# R205X.net
KiCad netlist of a schematic drawn in EAGLE
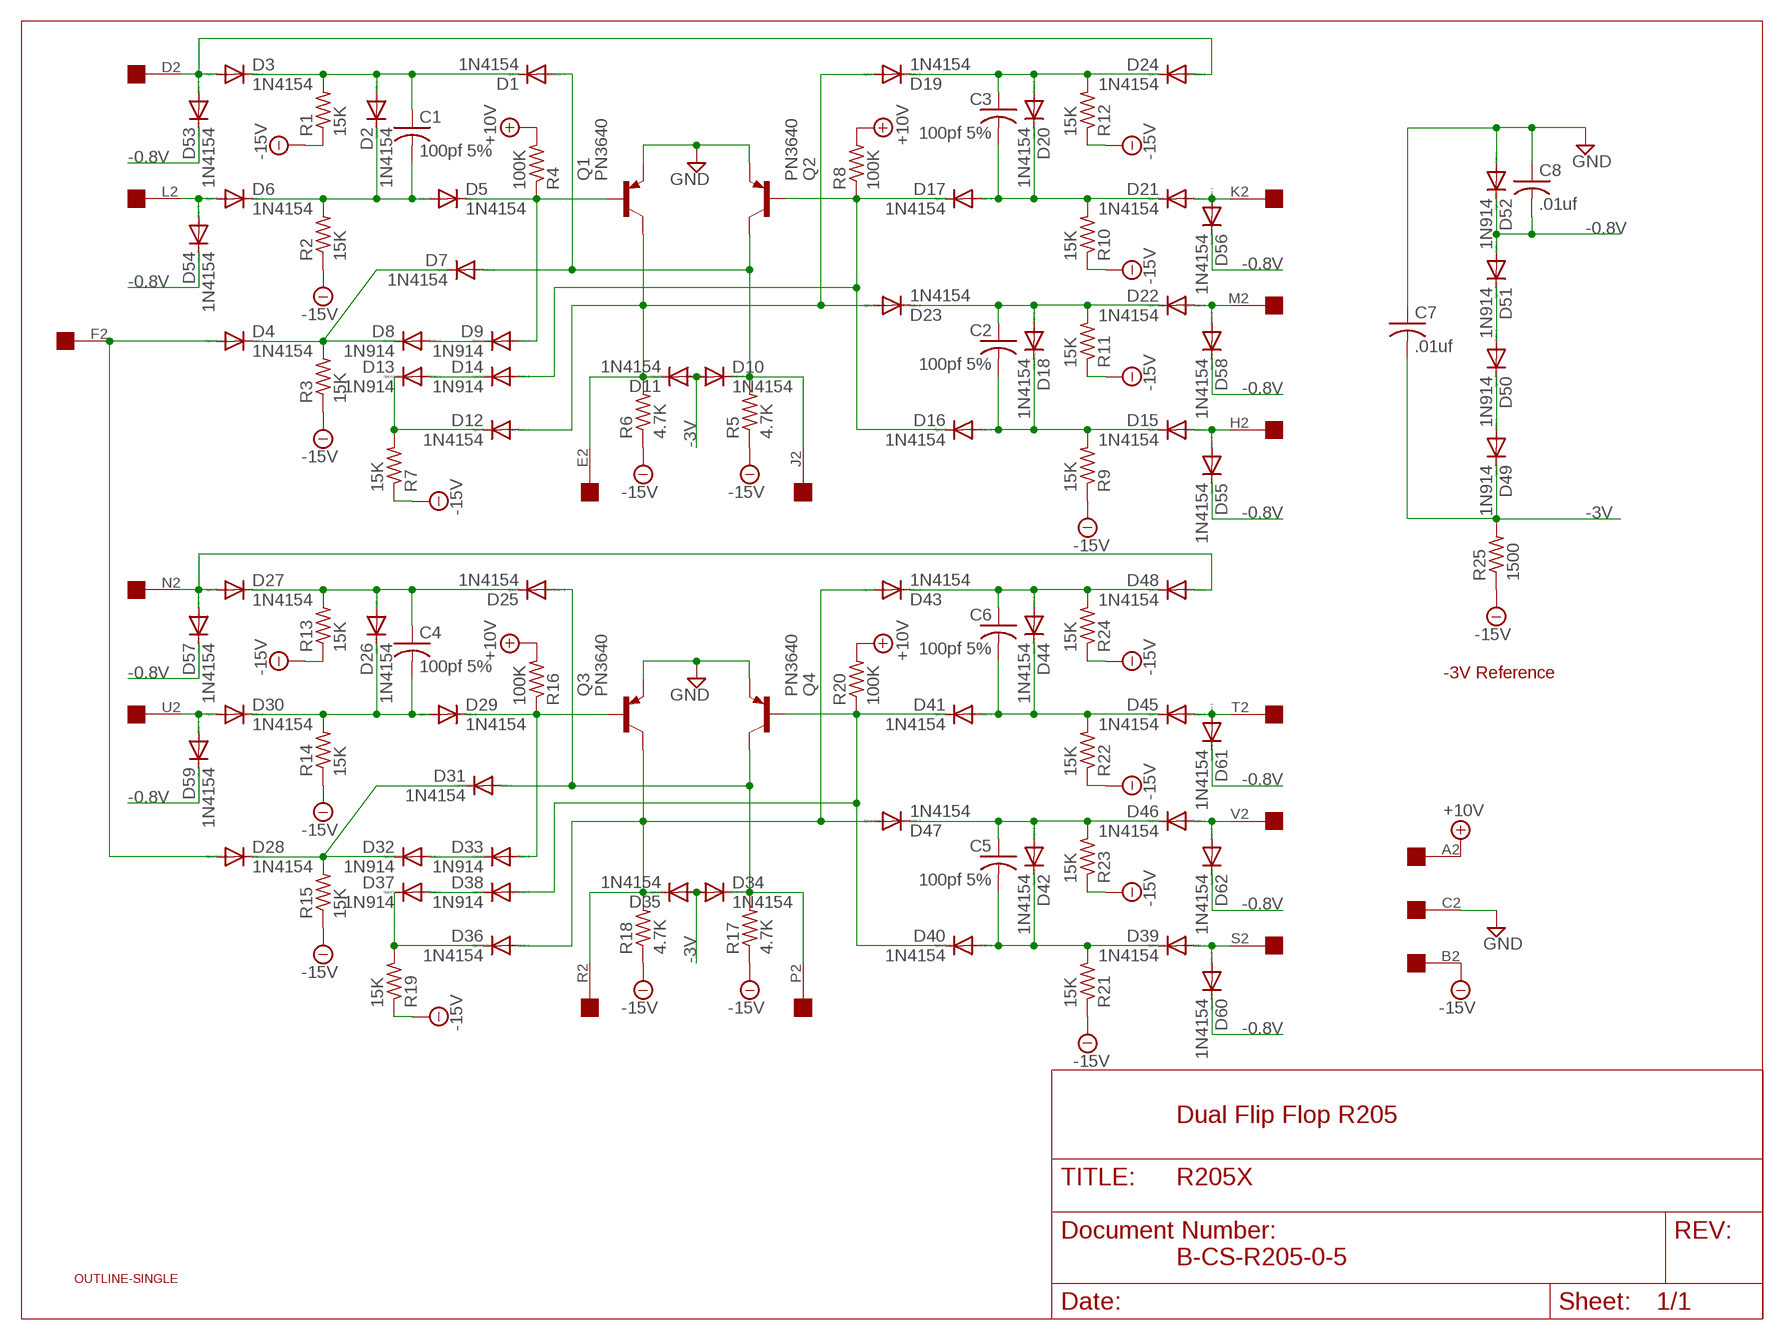
[diagram p0: schematic, sheet 1]

(export (version "E")
  (design (tool "Eeschema 10.0.6"))
  (components
    (comp (ref "C1")
      (value "100pf 5%")
      (footprint "eagle-import:C050-025X075")
      (libsource (lib "eagle-import") (part "C-US050-025X075"))
    )
    (comp (ref "C2")
      (value "100pf 5%")
      (footprint "eagle-import:C050-025X075")
      (libsource (lib "eagle-import") (part "C-US050-025X075"))
    )
    (comp (ref "C3")
      (value "100pf 5%")
      (footprint "eagle-import:C050-025X075")
      (libsource (lib "eagle-import") (part "C-US050-025X075"))
    )
    (comp (ref "C4")
      (value "100pf 5%")
      (footprint "eagle-import:C050-025X075")
      (libsource (lib "eagle-import") (part "C-US050-025X075"))
    )
    (comp (ref "C5")
      (value "100pf 5%")
      (footprint "eagle-import:C050-025X075")
      (libsource (lib "eagle-import") (part "C-US050-025X075"))
    )
    (comp (ref "C6")
      (value "100pf 5%")
      (footprint "eagle-import:C050-025X075")
      (libsource (lib "eagle-import") (part "C-US050-025X075"))
    )
    (comp (ref "C7")
      (value ".01uf")
      (footprint "eagle-import:C050-025X075")
      (libsource (lib "eagle-import") (part "C-US050-025X075"))
    )
    (comp (ref "C8")
      (value ".01uf")
      (footprint "eagle-import:C050-025X075")
      (libsource (lib "eagle-import") (part "C-US050-025X075"))
    )
    (comp (ref "D1")
      (value "1N4154")
      (footprint "eagle-import:DO35-10")
      (libsource (lib "eagle-import") (part "1N4148DO35-10"))
    )
    (comp (ref "D2")
      (value "1N4154")
      (footprint "eagle-import:DO35-10")
      (libsource (lib "eagle-import") (part "1N4148DO35-10"))
    )
    (comp (ref "D3")
      (value "1N4154")
      (footprint "eagle-import:DO35-10")
      (libsource (lib "eagle-import") (part "1N4148DO35-10"))
    )
    (comp (ref "D4")
      (value "1N4154")
      (footprint "eagle-import:DO35-10")
      (libsource (lib "eagle-import") (part "1N4148DO35-10"))
    )
    (comp (ref "D5")
      (value "1N4154")
      (footprint "eagle-import:DO35-10")
      (libsource (lib "eagle-import") (part "1N4148DO35-10"))
    )
    (comp (ref "D6")
      (value "1N4154")
      (footprint "eagle-import:DO35-10")
      (libsource (lib "eagle-import") (part "1N4148DO35-10"))
    )
    (comp (ref "D7")
      (value "1N4154")
      (footprint "eagle-import:DO35-10")
      (libsource (lib "eagle-import") (part "1N4148DO35-10"))
    )
    (comp (ref "D8")
      (value "1N914")
      (footprint "eagle-import:DO35-10")
      (libsource (lib "eagle-import") (part "1N4148DO35-10"))
    )
    (comp (ref "D9")
      (value "1N914")
      (footprint "eagle-import:DO35-10")
      (libsource (lib "eagle-import") (part "1N4148DO35-10"))
    )
    (comp (ref "D10")
      (value "1N4154")
      (footprint "eagle-import:DO35-10")
      (libsource (lib "eagle-import") (part "1N4148DO35-10"))
    )
    (comp (ref "D11")
      (value "1N4154")
      (footprint "eagle-import:DO35-10")
      (libsource (lib "eagle-import") (part "1N4148DO35-10"))
    )
    (comp (ref "D12")
      (value "1N4154")
      (footprint "eagle-import:DO35-10")
      (libsource (lib "eagle-import") (part "1N4148DO35-10"))
    )
    (comp (ref "D13")
      (value "1N914")
      (footprint "eagle-import:DO35-10")
      (libsource (lib "eagle-import") (part "1N4148DO35-10"))
    )
    (comp (ref "D14")
      (value "1N914")
      (footprint "eagle-import:DO35-10")
      (libsource (lib "eagle-import") (part "1N4148DO35-10"))
    )
    (comp (ref "D15")
      (value "1N4154")
      (footprint "eagle-import:DO35-10")
      (libsource (lib "eagle-import") (part "1N4148DO35-10"))
    )
    (comp (ref "D16")
      (value "1N4154")
      (footprint "eagle-import:DO35-10")
      (libsource (lib "eagle-import") (part "1N4148DO35-10"))
    )
    (comp (ref "D17")
      (value "1N4154")
      (footprint "eagle-import:DO35-10")
      (libsource (lib "eagle-import") (part "1N4148DO35-10"))
    )
    (comp (ref "D18")
      (value "1N4154")
      (footprint "eagle-import:DO35-10")
      (libsource (lib "eagle-import") (part "1N4148DO35-10"))
    )
    (comp (ref "D19")
      (value "1N4154")
      (footprint "eagle-import:DO35-10")
      (libsource (lib "eagle-import") (part "1N4148DO35-10"))
    )
    (comp (ref "D20")
      (value "1N4154")
      (footprint "eagle-import:DO35-10")
      (libsource (lib "eagle-import") (part "1N4148DO35-10"))
    )
    (comp (ref "D21")
      (value "1N4154")
      (footprint "eagle-import:DO35-10")
      (libsource (lib "eagle-import") (part "1N4148DO35-10"))
    )
    (comp (ref "D22")
      (value "1N4154")
      (footprint "eagle-import:DO35-10")
      (libsource (lib "eagle-import") (part "1N4148DO35-10"))
    )
    (comp (ref "D23")
      (value "1N4154")
      (footprint "eagle-import:DO35-10")
      (libsource (lib "eagle-import") (part "1N4148DO35-10"))
    )
    (comp (ref "D24")
      (value "1N4154")
      (footprint "eagle-import:DO35-10")
      (libsource (lib "eagle-import") (part "1N4148DO35-10"))
    )
    (comp (ref "D25")
      (value "1N4154")
      (footprint "eagle-import:DO35-10")
      (libsource (lib "eagle-import") (part "1N4148DO35-10"))
    )
    (comp (ref "D26")
      (value "1N4154")
      (footprint "eagle-import:DO35-10")
      (libsource (lib "eagle-import") (part "1N4148DO35-10"))
    )
    (comp (ref "D27")
      (value "1N4154")
      (footprint "eagle-import:DO35-10")
      (libsource (lib "eagle-import") (part "1N4148DO35-10"))
    )
    (comp (ref "D28")
      (value "1N4154")
      (footprint "eagle-import:DO35-10")
      (libsource (lib "eagle-import") (part "1N4148DO35-10"))
    )
    (comp (ref "D29")
      (value "1N4154")
      (footprint "eagle-import:DO35-10")
      (libsource (lib "eagle-import") (part "1N4148DO35-10"))
    )
    (comp (ref "D30")
      (value "1N4154")
      (footprint "eagle-import:DO35-10")
      (libsource (lib "eagle-import") (part "1N4148DO35-10"))
    )
    (comp (ref "D31")
      (value "1N4154")
      (footprint "eagle-import:DO35-10")
      (libsource (lib "eagle-import") (part "1N4148DO35-10"))
    )
    (comp (ref "D32")
      (value "1N914")
      (footprint "eagle-import:DO35-10")
      (libsource (lib "eagle-import") (part "1N4148DO35-10"))
    )
    (comp (ref "D33")
      (value "1N914")
      (footprint "eagle-import:DO35-10")
      (libsource (lib "eagle-import") (part "1N4148DO35-10"))
    )
    (comp (ref "D34")
      (value "1N4154")
      (footprint "eagle-import:DO35-10")
      (libsource (lib "eagle-import") (part "1N4148DO35-10"))
    )
    (comp (ref "D35")
      (value "1N4154")
      (footprint "eagle-import:DO35-10")
      (libsource (lib "eagle-import") (part "1N4148DO35-10"))
    )
    (comp (ref "D36")
      (value "1N4154")
      (footprint "eagle-import:DO35-10")
      (libsource (lib "eagle-import") (part "1N4148DO35-10"))
    )
    (comp (ref "D37")
      (value "1N914")
      (footprint "eagle-import:DO35-10")
      (libsource (lib "eagle-import") (part "1N4148DO35-10"))
    )
    (comp (ref "D38")
      (value "1N914")
      (footprint "eagle-import:DO35-10")
      (libsource (lib "eagle-import") (part "1N4148DO35-10"))
    )
    (comp (ref "D39")
      (value "1N4154")
      (footprint "eagle-import:DO35-10")
      (libsource (lib "eagle-import") (part "1N4148DO35-10"))
    )
    (comp (ref "D40")
      (value "1N4154")
      (footprint "eagle-import:DO35-10")
      (libsource (lib "eagle-import") (part "1N4148DO35-10"))
    )
    (comp (ref "D41")
      (value "1N4154")
      (footprint "eagle-import:DO35-10")
      (libsource (lib "eagle-import") (part "1N4148DO35-10"))
    )
    (comp (ref "D42")
      (value "1N4154")
      (footprint "eagle-import:DO35-10")
      (libsource (lib "eagle-import") (part "1N4148DO35-10"))
    )
    (comp (ref "D43")
      (value "1N4154")
      (footprint "eagle-import:DO35-10")
      (libsource (lib "eagle-import") (part "1N4148DO35-10"))
    )
    (comp (ref "D44")
      (value "1N4154")
      (footprint "eagle-import:DO35-10")
      (libsource (lib "eagle-import") (part "1N4148DO35-10"))
    )
    (comp (ref "D45")
      (value "1N4154")
      (footprint "eagle-import:DO35-10")
      (libsource (lib "eagle-import") (part "1N4148DO35-10"))
    )
    (comp (ref "D46")
      (value "1N4154")
      (footprint "eagle-import:DO35-10")
      (libsource (lib "eagle-import") (part "1N4148DO35-10"))
    )
    (comp (ref "D47")
      (value "1N4154")
      (footprint "eagle-import:DO35-10")
      (libsource (lib "eagle-import") (part "1N4148DO35-10"))
    )
    (comp (ref "D48")
      (value "1N4154")
      (footprint "eagle-import:DO35-10")
      (libsource (lib "eagle-import") (part "1N4148DO35-10"))
    )
    (comp (ref "D49")
      (value "1N914")
      (footprint "eagle-import:DO35-10")
      (libsource (lib "eagle-import") (part "1N4148DO35-10"))
    )
    (comp (ref "D50")
      (value "1N914")
      (footprint "eagle-import:DO35-10")
      (libsource (lib "eagle-import") (part "1N4148DO35-10"))
    )
    (comp (ref "D51")
      (value "1N914")
      (footprint "eagle-import:DO35-10")
      (libsource (lib "eagle-import") (part "1N4148DO35-10"))
    )
    (comp (ref "D52")
      (value "1N914")
      (footprint "eagle-import:DO35-10")
      (libsource (lib "eagle-import") (part "1N4148DO35-10"))
    )
    (comp (ref "D53")
      (value "1N4154")
      (footprint "eagle-import:DO35-10")
      (libsource (lib "eagle-import") (part "1N4148DO35-10"))
    )
    (comp (ref "D54")
      (value "1N4154")
      (footprint "eagle-import:DO35-10")
      (libsource (lib "eagle-import") (part "1N4148DO35-10"))
    )
    (comp (ref "D55")
      (value "1N4154")
      (footprint "eagle-import:DO35-10")
      (libsource (lib "eagle-import") (part "1N4148DO35-10"))
    )
    (comp (ref "D56")
      (value "1N4154")
      (footprint "eagle-import:DO35-10")
      (libsource (lib "eagle-import") (part "1N4148DO35-10"))
    )
    (comp (ref "D57")
      (value "1N4154")
      (footprint "eagle-import:DO35-10")
      (libsource (lib "eagle-import") (part "1N4148DO35-10"))
    )
    (comp (ref "D58")
      (value "1N4154")
      (footprint "eagle-import:DO35-10")
      (libsource (lib "eagle-import") (part "1N4148DO35-10"))
    )
    (comp (ref "D59")
      (value "1N4154")
      (footprint "eagle-import:DO35-10")
      (libsource (lib "eagle-import") (part "1N4148DO35-10"))
    )
    (comp (ref "D60")
      (value "1N4154")
      (footprint "eagle-import:DO35-10")
      (libsource (lib "eagle-import") (part "1N4148DO35-10"))
    )
    (comp (ref "D61")
      (value "1N4154")
      (footprint "eagle-import:DO35-10")
      (libsource (lib "eagle-import") (part "1N4148DO35-10"))
    )
    (comp (ref "D62")
      (value "1N4154")
      (footprint "eagle-import:DO35-10")
      (libsource (lib "eagle-import") (part "1N4148DO35-10"))
    )
    (comp (ref "Q1")
      (value "PN3640")
      (footprint "eagle-import:TO39")
      (libsource (lib "eagle-import") (part "2N3637"))
    )
    (comp (ref "Q2")
      (value "PN3640")
      (footprint "eagle-import:TO39")
      (libsource (lib "eagle-import") (part "2N3637"))
    )
    (comp (ref "Q3")
      (value "PN3640")
      (footprint "eagle-import:TO39")
      (libsource (lib "eagle-import") (part "2N3637"))
    )
    (comp (ref "Q4")
      (value "PN3640")
      (footprint "eagle-import:TO39")
      (libsource (lib "eagle-import") (part "2N3637"))
    )
    (comp (ref "R1")
      (value "15K")
      (footprint "eagle-import:0207_10")
      (libsource (lib "eagle-import") (part "R-US_0207/10"))
    )
    (comp (ref "R2")
      (value "15K")
      (footprint "eagle-import:0207_10")
      (libsource (lib "eagle-import") (part "R-US_0207/10"))
    )
    (comp (ref "R3")
      (value "15K")
      (footprint "eagle-import:0207_10")
      (libsource (lib "eagle-import") (part "R-US_0207/10"))
    )
    (comp (ref "R4")
      (value "100K")
      (footprint "eagle-import:0207_10")
      (libsource (lib "eagle-import") (part "R-US_0207/10"))
    )
    (comp (ref "R5")
      (value "4.7K")
      (footprint "eagle-import:0207_10")
      (libsource (lib "eagle-import") (part "R-US_0207/10"))
    )
    (comp (ref "R6")
      (value "4.7K")
      (footprint "eagle-import:0207_10")
      (libsource (lib "eagle-import") (part "R-US_0207/10"))
    )
    (comp (ref "R7")
      (value "15K")
      (footprint "eagle-import:0207_10")
      (libsource (lib "eagle-import") (part "R-US_0207/10"))
    )
    (comp (ref "R8")
      (value "100K")
      (footprint "eagle-import:0207_10")
      (libsource (lib "eagle-import") (part "R-US_0207/10"))
    )
    (comp (ref "R9")
      (value "15K")
      (footprint "eagle-import:0207_10")
      (libsource (lib "eagle-import") (part "R-US_0207/10"))
    )
    (comp (ref "R10")
      (value "15K")
      (footprint "eagle-import:0207_10")
      (libsource (lib "eagle-import") (part "R-US_0207/10"))
    )
    (comp (ref "R11")
      (value "15K")
      (footprint "eagle-import:0207_10")
      (libsource (lib "eagle-import") (part "R-US_0207/10"))
    )
    (comp (ref "R12")
      (value "15K")
      (footprint "eagle-import:0207_10")
      (libsource (lib "eagle-import") (part "R-US_0207/10"))
    )
    (comp (ref "R13")
      (value "15K")
      (footprint "eagle-import:0207_10")
      (libsource (lib "eagle-import") (part "R-US_0207/10"))
    )
    (comp (ref "R14")
      (value "15K")
      (footprint "eagle-import:0207_10")
      (libsource (lib "eagle-import") (part "R-US_0207/10"))
    )
    (comp (ref "R15")
      (value "15K")
      (footprint "eagle-import:0207_10")
      (libsource (lib "eagle-import") (part "R-US_0207/10"))
    )
    (comp (ref "R16")
      (value "100K")
      (footprint "eagle-import:0207_10")
      (libsource (lib "eagle-import") (part "R-US_0207/10"))
    )
    (comp (ref "R17")
      (value "4.7K")
      (footprint "eagle-import:0207_10")
      (libsource (lib "eagle-import") (part "R-US_0207/10"))
    )
    (comp (ref "R18")
      (value "4.7K")
      (footprint "eagle-import:0207_10")
      (libsource (lib "eagle-import") (part "R-US_0207/10"))
    )
    (comp (ref "R19")
      (value "15K")
      (footprint "eagle-import:0207_10")
      (libsource (lib "eagle-import") (part "R-US_0207/10"))
    )
    (comp (ref "R20")
      (value "100K")
      (footprint "eagle-import:0207_10")
      (libsource (lib "eagle-import") (part "R-US_0207/10"))
    )
    (comp (ref "R21")
      (value "15K")
      (footprint "eagle-import:0207_10")
      (libsource (lib "eagle-import") (part "R-US_0207/10"))
    )
    (comp (ref "R22")
      (value "15K")
      (footprint "eagle-import:0207_10")
      (libsource (lib "eagle-import") (part "R-US_0207/10"))
    )
    (comp (ref "R23")
      (value "15K")
      (footprint "eagle-import:0207_10")
      (libsource (lib "eagle-import") (part "R-US_0207/10"))
    )
    (comp (ref "R24")
      (value "15K")
      (footprint "eagle-import:0207_10")
      (libsource (lib "eagle-import") (part "R-US_0207/10"))
    )
    (comp (ref "R25")
      (value "1500")
      (footprint "eagle-import:0207_10")
      (libsource (lib "eagle-import") (part "R-US_0207/10"))
    )
    (comp (ref "U$1")
      (value "OUTLINE-SINGLE")
      (footprint "eagle-import:SINGLE")
      (libsource (lib "eagle-import") (part "OUTLINE-SINGLE"))
    )
    (comp (ref "U$2")
      (value "EDGE-1")
      (footprint "eagle-import:EDGE-CON1")
      (libsource (lib "eagle-import") (part "EDGE-1"))
    )
  )
  (nets
    (net (code "1") (name "+10V") (class "Default")
      (node (ref "R16") (pin "2") (pinfunction "2_2") (pintype "passive"))
      (node (ref "R20") (pin "2") (pinfunction "2_2") (pintype "passive"))
      (node (ref "R4") (pin "2") (pinfunction "2_2") (pintype "passive"))
      (node (ref "R8") (pin "2") (pinfunction "2_2") (pintype "passive"))
      (node (ref "U$2") (pin "A2") (pinfunction "1_A2") (pintype "bidirectional"))
    )
    (net (code "2") (name "-15V") (class "Default")
      (node (ref "R1") (pin "1") (pinfunction "1_1") (pintype "passive"))
      (node (ref "R10") (pin "1") (pinfunction "1_1") (pintype "passive"))
      (node (ref "R11") (pin "1") (pinfunction "1_1") (pintype "passive"))
      (node (ref "R12") (pin "1") (pinfunction "1_1") (pintype "passive"))
      (node (ref "R13") (pin "1") (pinfunction "1_1") (pintype "passive"))
      (node (ref "R14") (pin "1") (pinfunction "1_1") (pintype "passive"))
      (node (ref "R15") (pin "1") (pinfunction "1_1") (pintype "passive"))
      (node (ref "R17") (pin "1") (pinfunction "1_1") (pintype "passive"))
      (node (ref "R18") (pin "1") (pinfunction "1_1") (pintype "passive"))
      (node (ref "R19") (pin "1") (pinfunction "1_1") (pintype "passive"))
      (node (ref "R2") (pin "1") (pinfunction "1_1") (pintype "passive"))
      (node (ref "R21") (pin "1") (pinfunction "1_1") (pintype "passive"))
      (node (ref "R22") (pin "1") (pinfunction "1_1") (pintype "passive"))
      (node (ref "R23") (pin "1") (pinfunction "1_1") (pintype "passive"))
      (node (ref "R24") (pin "1") (pinfunction "1_1") (pintype "passive"))
      (node (ref "R25") (pin "1") (pinfunction "1_1") (pintype "passive"))
      (node (ref "R3") (pin "1") (pinfunction "1_1") (pintype "passive"))
      (node (ref "R5") (pin "1") (pinfunction "1_1") (pintype "passive"))
      (node (ref "R6") (pin "1") (pinfunction "1_1") (pintype "passive"))
      (node (ref "R7") (pin "1") (pinfunction "1_1") (pintype "passive"))
      (node (ref "R9") (pin "1") (pinfunction "1_1") (pintype "passive"))
      (node (ref "U$2") (pin "B2") (pinfunction "1_B2") (pintype "bidirectional"))
    )
    (net (code "3") (name "/-0.8V") (class "Default")
      (node (ref "C8") (pin "2") (pinfunction "2_2") (pintype "passive"))
      (node (ref "D51") (pin "A") (pinfunction "A_A") (pintype "passive"))
      (node (ref "D52") (pin "C") (pinfunction "C_C") (pintype "passive"))
      (node (ref "D53") (pin "C") (pinfunction "C_C") (pintype "passive"))
      (node (ref "D54") (pin "C") (pinfunction "C_C") (pintype "passive"))
      (node (ref "D55") (pin "C") (pinfunction "C_C") (pintype "passive"))
      (node (ref "D56") (pin "C") (pinfunction "C_C") (pintype "passive"))
      (node (ref "D57") (pin "C") (pinfunction "C_C") (pintype "passive"))
      (node (ref "D58") (pin "C") (pinfunction "C_C") (pintype "passive"))
      (node (ref "D59") (pin "C") (pinfunction "C_C") (pintype "passive"))
      (node (ref "D60") (pin "C") (pinfunction "C_C") (pintype "passive"))
      (node (ref "D61") (pin "C") (pinfunction "C_C") (pintype "passive"))
      (node (ref "D62") (pin "C") (pinfunction "C_C") (pintype "passive"))
    )
    (net (code "4") (name "/-3V") (class "Default")
      (node (ref "C7") (pin "2") (pinfunction "2_2") (pintype "passive"))
      (node (ref "D10") (pin "A") (pinfunction "A_A") (pintype "passive"))
      (node (ref "D11") (pin "A") (pinfunction "A_A") (pintype "passive"))
      (node (ref "D34") (pin "A") (pinfunction "A_A") (pintype "passive"))
      (node (ref "D35") (pin "A") (pinfunction "A_A") (pintype "passive"))
      (node (ref "D49") (pin "C") (pinfunction "C_C") (pintype "passive"))
      (node (ref "R25") (pin "2") (pinfunction "2_2") (pintype "passive"))
    )
    (net (code "5") (name "GND") (class "Default")
      (node (ref "C7") (pin "1") (pinfunction "1_1") (pintype "passive"))
      (node (ref "C8") (pin "1") (pinfunction "1_1") (pintype "passive"))
      (node (ref "D52") (pin "A") (pinfunction "A_A") (pintype "passive"))
      (node (ref "Q1") (pin "1") (pinfunction "E_1") (pintype "passive"))
      (node (ref "Q2") (pin "1") (pinfunction "E_1") (pintype "passive"))
      (node (ref "Q3") (pin "1") (pinfunction "E_1") (pintype "passive"))
      (node (ref "Q4") (pin "1") (pinfunction "E_1") (pintype "passive"))
      (node (ref "U$2") (pin "C2") (pinfunction "1_C2") (pintype "bidirectional"))
    )
    (net (code "6") (name "Net-(C1-Pad1)") (class "Default")
      (node (ref "C1") (pin "1") (pinfunction "1_1") (pintype "passive"))
      (node (ref "D1") (pin "C") (pinfunction "C_C") (pintype "passive"))
      (node (ref "D2") (pin "A") (pinfunction "A_A") (pintype "passive"))
      (node (ref "D3") (pin "C") (pinfunction "C_C") (pintype "passive"))
      (node (ref "R1") (pin "2") (pinfunction "2_2") (pintype "passive"))
    )
    (net (code "7") (name "Net-(C1-Pad2)") (class "Default")
      (node (ref "C1") (pin "2") (pinfunction "2_2") (pintype "passive"))
      (node (ref "D2") (pin "C") (pinfunction "C_C") (pintype "passive"))
      (node (ref "D5") (pin "A") (pinfunction "A_A") (pintype "passive"))
      (node (ref "D6") (pin "C") (pinfunction "C_C") (pintype "passive"))
      (node (ref "R2") (pin "2") (pinfunction "2_2") (pintype "passive"))
    )
    (net (code "8") (name "Net-(C2-Pad1)") (class "Default")
      (node (ref "C2") (pin "1") (pinfunction "1_1") (pintype "passive"))
      (node (ref "D18") (pin "A") (pinfunction "A_A") (pintype "passive"))
      (node (ref "D22") (pin "C") (pinfunction "C_C") (pintype "passive"))
      (node (ref "D23") (pin "C") (pinfunction "C_C") (pintype "passive"))
      (node (ref "R11") (pin "2") (pinfunction "2_2") (pintype "passive"))
    )
    (net (code "9") (name "Net-(C2-Pad2)") (class "Default")
      (node (ref "C2") (pin "2") (pinfunction "2_2") (pintype "passive"))
      (node (ref "D15") (pin "C") (pinfunction "C_C") (pintype "passive"))
      (node (ref "D16") (pin "A") (pinfunction "A_A") (pintype "passive"))
      (node (ref "D18") (pin "C") (pinfunction "C_C") (pintype "passive"))
      (node (ref "R9") (pin "2") (pinfunction "2_2") (pintype "passive"))
    )
    (net (code "10") (name "Net-(C3-Pad1)") (class "Default")
      (node (ref "C3") (pin "1") (pinfunction "1_1") (pintype "passive"))
      (node (ref "D19") (pin "C") (pinfunction "C_C") (pintype "passive"))
      (node (ref "D20") (pin "A") (pinfunction "A_A") (pintype "passive"))
      (node (ref "D24") (pin "C") (pinfunction "C_C") (pintype "passive"))
      (node (ref "R12") (pin "2") (pinfunction "2_2") (pintype "passive"))
    )
    (net (code "11") (name "Net-(C3-Pad2)") (class "Default")
      (node (ref "C3") (pin "2") (pinfunction "2_2") (pintype "passive"))
      (node (ref "D17") (pin "A") (pinfunction "A_A") (pintype "passive"))
      (node (ref "D20") (pin "C") (pinfunction "C_C") (pintype "passive"))
      (node (ref "D21") (pin "C") (pinfunction "C_C") (pintype "passive"))
      (node (ref "R10") (pin "2") (pinfunction "2_2") (pintype "passive"))
    )
    (net (code "12") (name "Net-(C4-Pad1)") (class "Default")
      (node (ref "C4") (pin "1") (pinfunction "1_1") (pintype "passive"))
      (node (ref "D25") (pin "C") (pinfunction "C_C") (pintype "passive"))
      (node (ref "D26") (pin "A") (pinfunction "A_A") (pintype "passive"))
      (node (ref "D27") (pin "C") (pinfunction "C_C") (pintype "passive"))
      (node (ref "R13") (pin "2") (pinfunction "2_2") (pintype "passive"))
    )
    (net (code "13") (name "Net-(C4-Pad2)") (class "Default")
      (node (ref "C4") (pin "2") (pinfunction "2_2") (pintype "passive"))
      (node (ref "D26") (pin "C") (pinfunction "C_C") (pintype "passive"))
      (node (ref "D29") (pin "A") (pinfunction "A_A") (pintype "passive"))
      (node (ref "D30") (pin "C") (pinfunction "C_C") (pintype "passive"))
      (node (ref "R14") (pin "2") (pinfunction "2_2") (pintype "passive"))
    )
    (net (code "14") (name "Net-(C5-Pad1)") (class "Default")
      (node (ref "C5") (pin "1") (pinfunction "1_1") (pintype "passive"))
      (node (ref "D42") (pin "A") (pinfunction "A_A") (pintype "passive"))
      (node (ref "D46") (pin "C") (pinfunction "C_C") (pintype "passive"))
      (node (ref "D47") (pin "C") (pinfunction "C_C") (pintype "passive"))
      (node (ref "R23") (pin "2") (pinfunction "2_2") (pintype "passive"))
    )
    (net (code "15") (name "Net-(C5-Pad2)") (class "Default")
      (node (ref "C5") (pin "2") (pinfunction "2_2") (pintype "passive"))
      (node (ref "D39") (pin "C") (pinfunction "C_C") (pintype "passive"))
      (node (ref "D40") (pin "A") (pinfunction "A_A") (pintype "passive"))
      (node (ref "D42") (pin "C") (pinfunction "C_C") (pintype "passive"))
      (node (ref "R21") (pin "2") (pinfunction "2_2") (pintype "passive"))
    )
    (net (code "16") (name "Net-(C6-Pad1)") (class "Default")
      (node (ref "C6") (pin "1") (pinfunction "1_1") (pintype "passive"))
      (node (ref "D43") (pin "C") (pinfunction "C_C") (pintype "passive"))
      (node (ref "D44") (pin "A") (pinfunction "A_A") (pintype "passive"))
      (node (ref "D48") (pin "C") (pinfunction "C_C") (pintype "passive"))
      (node (ref "R24") (pin "2") (pinfunction "2_2") (pintype "passive"))
    )
    (net (code "17") (name "Net-(C6-Pad2)") (class "Default")
      (node (ref "C6") (pin "2") (pinfunction "2_2") (pintype "passive"))
      (node (ref "D41") (pin "A") (pinfunction "A_A") (pintype "passive"))
      (node (ref "D44") (pin "C") (pinfunction "C_C") (pintype "passive"))
      (node (ref "D45") (pin "C") (pinfunction "C_C") (pintype "passive"))
      (node (ref "R22") (pin "2") (pinfunction "2_2") (pintype "passive"))
    )
    (net (code "18") (name "Net-(D4-PadC)") (class "Default")
      (node (ref "D4") (pin "C") (pinfunction "C_C") (pintype "passive"))
      (node (ref "D7") (pin "C") (pinfunction "C_C") (pintype "passive"))
      (node (ref "D8") (pin "C") (pinfunction "C_C") (pintype "passive"))
      (node (ref "R3") (pin "2") (pinfunction "2_2") (pintype "passive"))
    )
    (net (code "19") (name "Net-(D8-PadA)") (class "Default")
      (node (ref "D8") (pin "A") (pinfunction "A_A") (pintype "passive"))
      (node (ref "D9") (pin "C") (pinfunction "C_C") (pintype "passive"))
    )
    (net (code "20") (name "Net-(D12-PadC)") (class "Default")
      (node (ref "D12") (pin "C") (pinfunction "C_C") (pintype "passive"))
      (node (ref "D13") (pin "C") (pinfunction "C_C") (pintype "passive"))
      (node (ref "R7") (pin "2") (pinfunction "2_2") (pintype "passive"))
    )
    (net (code "21") (name "Net-(D13-PadA)") (class "Default")
      (node (ref "D13") (pin "A") (pinfunction "A_A") (pintype "passive"))
      (node (ref "D14") (pin "C") (pinfunction "C_C") (pintype "passive"))
    )
    (net (code "22") (name "Net-(D28-PadC)") (class "Default")
      (node (ref "D28") (pin "C") (pinfunction "C_C") (pintype "passive"))
      (node (ref "D31") (pin "C") (pinfunction "C_C") (pintype "passive"))
      (node (ref "D32") (pin "C") (pinfunction "C_C") (pintype "passive"))
      (node (ref "R15") (pin "2") (pinfunction "2_2") (pintype "passive"))
    )
    (net (code "23") (name "Net-(D32-PadA)") (class "Default")
      (node (ref "D32") (pin "A") (pinfunction "A_A") (pintype "passive"))
      (node (ref "D33") (pin "C") (pinfunction "C_C") (pintype "passive"))
    )
    (net (code "24") (name "Net-(D36-PadC)") (class "Default")
      (node (ref "D36") (pin "C") (pinfunction "C_C") (pintype "passive"))
      (node (ref "D37") (pin "C") (pinfunction "C_C") (pintype "passive"))
      (node (ref "R19") (pin "2") (pinfunction "2_2") (pintype "passive"))
    )
    (net (code "25") (name "Net-(D37-PadA)") (class "Default")
      (node (ref "D37") (pin "A") (pinfunction "A_A") (pintype "passive"))
      (node (ref "D38") (pin "C") (pinfunction "C_C") (pintype "passive"))
    )
    (net (code "26") (name "Net-(D49-PadA)") (class "Default")
      (node (ref "D49") (pin "A") (pinfunction "A_A") (pintype "passive"))
      (node (ref "D50") (pin "C") (pinfunction "C_C") (pintype "passive"))
    )
    (net (code "27") (name "Net-(D50-PadA)") (class "Default")
      (node (ref "D50") (pin "A") (pinfunction "A_A") (pintype "passive"))
      (node (ref "D51") (pin "C") (pinfunction "C_C") (pintype "passive"))
    )
    (net (code "28") (name "Net-(Q1-B)") (class "Default")
      (node (ref "D5") (pin "C") (pinfunction "C_C") (pintype "passive"))
      (node (ref "D9") (pin "A") (pinfunction "A_A") (pintype "passive"))
      (node (ref "Q1") (pin "2") (pinfunction "B_2") (pintype "passive"))
      (node (ref "R4") (pin "1") (pinfunction "1_1") (pintype "passive"))
    )
    (net (code "29") (name "Net-(Q1-C)") (class "Default")
      (node (ref "D11") (pin "C") (pinfunction "C_C") (pintype "passive"))
      (node (ref "D12") (pin "A") (pinfunction "A_A") (pintype "passive"))
      (node (ref "D19") (pin "A") (pinfunction "A_A") (pintype "passive"))
      (node (ref "D23") (pin "A") (pinfunction "A_A") (pintype "passive"))
      (node (ref "Q1") (pin "3") (pinfunction "C_3") (pintype "passive"))
      (node (ref "R6") (pin "2") (pinfunction "2_2") (pintype "passive"))
      (node (ref "U$2") (pin "E2") (pinfunction "1_E2") (pintype "bidirectional"))
    )
    (net (code "30") (name "Net-(Q2-B)") (class "Default")
      (node (ref "D14") (pin "A") (pinfunction "A_A") (pintype "passive"))
      (node (ref "D16") (pin "C") (pinfunction "C_C") (pintype "passive"))
      (node (ref "D17") (pin "C") (pinfunction "C_C") (pintype "passive"))
      (node (ref "Q2") (pin "2") (pinfunction "B_2") (pintype "passive"))
      (node (ref "R8") (pin "1") (pinfunction "1_1") (pintype "passive"))
    )
    (net (code "31") (name "Net-(Q2-C)") (class "Default")
      (node (ref "D1") (pin "A") (pinfunction "A_A") (pintype "passive"))
      (node (ref "D10") (pin "C") (pinfunction "C_C") (pintype "passive"))
      (node (ref "D7") (pin "A") (pinfunction "A_A") (pintype "passive"))
      (node (ref "Q2") (pin "3") (pinfunction "C_3") (pintype "passive"))
      (node (ref "R5") (pin "2") (pinfunction "2_2") (pintype "passive"))
      (node (ref "U$2") (pin "J2") (pinfunction "1_J2") (pintype "bidirectional"))
    )
    (net (code "32") (name "Net-(Q3-B)") (class "Default")
      (node (ref "D29") (pin "C") (pinfunction "C_C") (pintype "passive"))
      (node (ref "D33") (pin "A") (pinfunction "A_A") (pintype "passive"))
      (node (ref "Q3") (pin "2") (pinfunction "B_2") (pintype "passive"))
      (node (ref "R16") (pin "1") (pinfunction "1_1") (pintype "passive"))
    )
    (net (code "33") (name "Net-(Q3-C)") (class "Default")
      (node (ref "D35") (pin "C") (pinfunction "C_C") (pintype "passive"))
      (node (ref "D36") (pin "A") (pinfunction "A_A") (pintype "passive"))
      (node (ref "D43") (pin "A") (pinfunction "A_A") (pintype "passive"))
      (node (ref "D47") (pin "A") (pinfunction "A_A") (pintype "passive"))
      (node (ref "Q3") (pin "3") (pinfunction "C_3") (pintype "passive"))
      (node (ref "R18") (pin "2") (pinfunction "2_2") (pintype "passive"))
      (node (ref "U$2") (pin "R2") (pinfunction "1_R2") (pintype "bidirectional"))
    )
    (net (code "34") (name "Net-(Q4-B)") (class "Default")
      (node (ref "D38") (pin "A") (pinfunction "A_A") (pintype "passive"))
      (node (ref "D40") (pin "C") (pinfunction "C_C") (pintype "passive"))
      (node (ref "D41") (pin "C") (pinfunction "C_C") (pintype "passive"))
      (node (ref "Q4") (pin "2") (pinfunction "B_2") (pintype "passive"))
      (node (ref "R20") (pin "1") (pinfunction "1_1") (pintype "passive"))
    )
    (net (code "35") (name "Net-(Q4-C)") (class "Default")
      (node (ref "D25") (pin "A") (pinfunction "A_A") (pintype "passive"))
      (node (ref "D31") (pin "A") (pinfunction "A_A") (pintype "passive"))
      (node (ref "D34") (pin "C") (pinfunction "C_C") (pintype "passive"))
      (node (ref "Q4") (pin "3") (pinfunction "C_3") (pintype "passive"))
      (node (ref "R17") (pin "2") (pinfunction "2_2") (pintype "passive"))
      (node (ref "U$2") (pin "P2") (pinfunction "1_P2") (pintype "bidirectional"))
    )
    (net (code "36") (name "Net-(U$2D-1)") (class "Default")
      (node (ref "D24") (pin "A") (pinfunction "A_A") (pintype "passive"))
      (node (ref "D3") (pin "A") (pinfunction "A_A") (pintype "passive"))
      (node (ref "D53") (pin "A") (pinfunction "A_A") (pintype "passive"))
      (node (ref "U$2") (pin "D2") (pinfunction "1_D2") (pintype "bidirectional"))
    )
    (net (code "37") (name "Net-(U$2F-1)") (class "Default")
      (node (ref "D28") (pin "A") (pinfunction "A_A") (pintype "passive"))
      (node (ref "D4") (pin "A") (pinfunction "A_A") (pintype "passive"))
      (node (ref "U$2") (pin "F2") (pinfunction "1_F2") (pintype "bidirectional"))
    )
    (net (code "38") (name "Net-(U$2G-1)") (class "Default")
      (node (ref "D15") (pin "A") (pinfunction "A_A") (pintype "passive"))
      (node (ref "D55") (pin "A") (pinfunction "A_A") (pintype "passive"))
      (node (ref "U$2") (pin "H2") (pinfunction "1_H2") (pintype "bidirectional"))
    )
    (net (code "39") (name "Net-(U$2I-1)") (class "Default")
      (node (ref "D21") (pin "A") (pinfunction "A_A") (pintype "passive"))
      (node (ref "D56") (pin "A") (pinfunction "A_A") (pintype "passive"))
      (node (ref "U$2") (pin "K2") (pinfunction "1_K2") (pintype "bidirectional"))
    )
    (net (code "40") (name "Net-(U$2J-1)") (class "Default")
      (node (ref "D54") (pin "A") (pinfunction "A_A") (pintype "passive"))
      (node (ref "D6") (pin "A") (pinfunction "A_A") (pintype "passive"))
      (node (ref "U$2") (pin "L2") (pinfunction "1_L2") (pintype "bidirectional"))
    )
    (net (code "41") (name "Net-(U$2K-1)") (class "Default")
      (node (ref "D22") (pin "A") (pinfunction "A_A") (pintype "passive"))
      (node (ref "D58") (pin "A") (pinfunction "A_A") (pintype "passive"))
      (node (ref "U$2") (pin "M2") (pinfunction "1_M2") (pintype "bidirectional"))
    )
    (net (code "42") (name "Net-(U$2L-1)") (class "Default")
      (node (ref "D27") (pin "A") (pinfunction "A_A") (pintype "passive"))
      (node (ref "D48") (pin "A") (pinfunction "A_A") (pintype "passive"))
      (node (ref "D57") (pin "A") (pinfunction "A_A") (pintype "passive"))
      (node (ref "U$2") (pin "N2") (pinfunction "1_N2") (pintype "bidirectional"))
    )
    (net (code "43") (name "Net-(U$2O-1)") (class "Default")
      (node (ref "D39") (pin "A") (pinfunction "A_A") (pintype "passive"))
      (node (ref "D60") (pin "A") (pinfunction "A_A") (pintype "passive"))
      (node (ref "U$2") (pin "S2") (pinfunction "1_S2") (pintype "bidirectional"))
    )
    (net (code "44") (name "Net-(U$2P-1)") (class "Default")
      (node (ref "D45") (pin "A") (pinfunction "A_A") (pintype "passive"))
      (node (ref "D61") (pin "A") (pinfunction "A_A") (pintype "passive"))
      (node (ref "U$2") (pin "T2") (pinfunction "1_T2") (pintype "bidirectional"))
    )
    (net (code "45") (name "Net-(U$2Q-1)") (class "Default")
      (node (ref "D30") (pin "A") (pinfunction "A_A") (pintype "passive"))
      (node (ref "D59") (pin "A") (pinfunction "A_A") (pintype "passive"))
      (node (ref "U$2") (pin "U2") (pinfunction "1_U2") (pintype "bidirectional"))
    )
    (net (code "46") (name "Net-(U$2R-1)") (class "Default")
      (node (ref "D46") (pin "A") (pinfunction "A_A") (pintype "passive"))
      (node (ref "D62") (pin "A") (pinfunction "A_A") (pintype "passive"))
      (node (ref "U$2") (pin "V2") (pinfunction "1_V2") (pintype "bidirectional"))
    )
  )
)
